# D2R.net
KiCad netlist of a schematic drawn in EAGLE
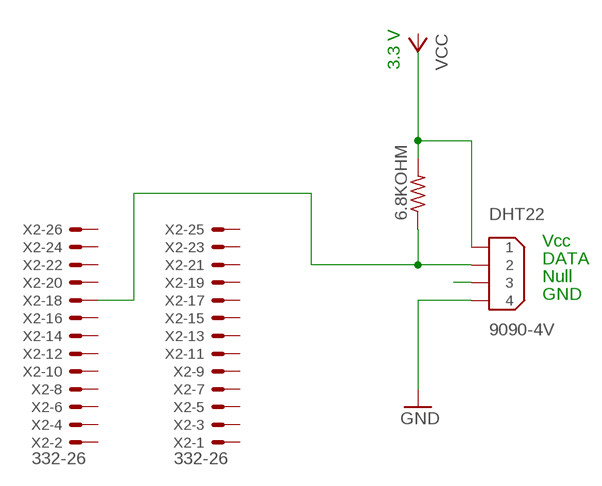
[diagram p0: schematic, sheet 1]

(export (version "E")
  (design (tool "Eeschema 10.0.6"))
  (components
    (comp (ref "6.8KOHM")
      (value "R-US_0207/10")
      (footprint "eagle-import:0207_10")
      (libsource (lib "eagle-import") (part "R-US_0207/10"))
    )
    (comp (ref "DHT22")
      (value "9090-4V")
      (footprint "eagle-import:9090-4V")
      (libsource (lib "eagle-import") (part "9090-4V"))
    )
    (comp (ref "X2")
      (value "332-26")
      (footprint "eagle-import:332-26")
      (libsource (lib "eagle-import") (part "332-26"))
    )
  )
  (nets
    (net (code "1") (name "GND") (class "Default")
      (node (ref "DHT22") (pin "4") (pinfunction "4_4") (pintype "passive"))
    )
    (net (code "2") (name "Net-(6.8KOHM-Pad2)") (class "Default")
      (node (ref "6.8KOHM") (pin "2") (pinfunction "2_2") (pintype "passive"))
      (node (ref "DHT22") (pin "1") (pinfunction "1_1") (pintype "passive"))
    )
    (net (code "3") (name "Net-(X2J-S)") (class "Default")
      (node (ref "6.8KOHM") (pin "1") (pinfunction "1_1") (pintype "passive"))
      (node (ref "DHT22") (pin "2") (pinfunction "2_2") (pintype "passive"))
      (node (ref "X2") (pin "18") (pinfunction "S_18") (pintype "passive"))
    )
    (net (code "5") (name "unconnected-(DHT22-Pad3)") (class "Default")
      (node (ref "DHT22") (pin "3") (pinfunction "3_3") (pintype "passive"))
    )
    (net (code "6") (name "unconnected-(X2A-S-Pad1)") (class "Default")
      (node (ref "X2") (pin "1") (pinfunction "S_1") (pintype "passive"))
    )
    (net (code "7") (name "unconnected-(X2B-S-Pad10)") (class "Default")
      (node (ref "X2") (pin "10") (pinfunction "S_10") (pintype "passive"))
    )
    (net (code "8") (name "unconnected-(X2C-S-Pad11)") (class "Default")
      (node (ref "X2") (pin "11") (pinfunction "S_11") (pintype "passive"))
    )
    (net (code "9") (name "unconnected-(X2D-S-Pad12)") (class "Default")
      (node (ref "X2") (pin "12") (pinfunction "S_12") (pintype "passive"))
    )
    (net (code "10") (name "unconnected-(X2E-S-Pad13)") (class "Default")
      (node (ref "X2") (pin "13") (pinfunction "S_13") (pintype "passive"))
    )
    (net (code "11") (name "unconnected-(X2F-S-Pad14)") (class "Default")
      (node (ref "X2") (pin "14") (pinfunction "S_14") (pintype "passive"))
    )
    (net (code "12") (name "unconnected-(X2G-S-Pad15)") (class "Default")
      (node (ref "X2") (pin "15") (pinfunction "S_15") (pintype "passive"))
    )
    (net (code "13") (name "unconnected-(X2H-S-Pad16)") (class "Default")
      (node (ref "X2") (pin "16") (pinfunction "S_16") (pintype "passive"))
    )
    (net (code "14") (name "unconnected-(X2I-S-Pad17)") (class "Default")
      (node (ref "X2") (pin "17") (pinfunction "S_17") (pintype "passive"))
    )
    (net (code "15") (name "unconnected-(X2K-S-Pad19)") (class "Default")
      (node (ref "X2") (pin "19") (pinfunction "S_19") (pintype "passive"))
    )
    (net (code "16") (name "unconnected-(X2L-S-Pad2)") (class "Default")
      (node (ref "X2") (pin "2") (pinfunction "S_2") (pintype "passive"))
    )
    (net (code "17") (name "unconnected-(X2M-S-Pad20)") (class "Default")
      (node (ref "X2") (pin "20") (pinfunction "S_20") (pintype "passive"))
    )
    (net (code "18") (name "unconnected-(X2N-S-Pad21)") (class "Default")
      (node (ref "X2") (pin "21") (pinfunction "S_21") (pintype "passive"))
    )
    (net (code "19") (name "unconnected-(X2O-S-Pad22)") (class "Default")
      (node (ref "X2") (pin "22") (pinfunction "S_22") (pintype "passive"))
    )
    (net (code "20") (name "unconnected-(X2P-S-Pad23)") (class "Default")
      (node (ref "X2") (pin "23") (pinfunction "S_23") (pintype "passive"))
    )
    (net (code "21") (name "unconnected-(X2Q-S-Pad24)") (class "Default")
      (node (ref "X2") (pin "24") (pinfunction "S_24") (pintype "passive"))
    )
    (net (code "22") (name "unconnected-(X2R-S-Pad25)") (class "Default")
      (node (ref "X2") (pin "25") (pinfunction "S_25") (pintype "passive"))
    )
    (net (code "23") (name "unconnected-(X2S-S-Pad26)") (class "Default")
      (node (ref "X2") (pin "26") (pinfunction "S_26") (pintype "passive"))
    )
    (net (code "24") (name "unconnected-(X2T-S-Pad3)") (class "Default")
      (node (ref "X2") (pin "3") (pinfunction "S_3") (pintype "passive"))
    )
    (net (code "25") (name "unconnected-(X2U-S-Pad4)") (class "Default")
      (node (ref "X2") (pin "4") (pinfunction "S_4") (pintype "passive"))
    )
    (net (code "26") (name "unconnected-(X2V-S-Pad5)") (class "Default")
      (node (ref "X2") (pin "5") (pinfunction "S_5") (pintype "passive"))
    )
    (net (code "27") (name "unconnected-(X2W-S-Pad6)") (class "Default")
      (node (ref "X2") (pin "6") (pinfunction "S_6") (pintype "passive"))
    )
    (net (code "28") (name "unconnected-(X2X-S-Pad7)") (class "Default")
      (node (ref "X2") (pin "7") (pinfunction "S_7") (pintype "passive"))
    )
    (net (code "29") (name "unconnected-(X2Y-S-Pad8)") (class "Default")
      (node (ref "X2") (pin "8") (pinfunction "S_8") (pintype "passive"))
    )
    (net (code "30") (name "unconnected-(X2Z-S-Pad9)") (class "Default")
      (node (ref "X2") (pin "9") (pinfunction "S_9") (pintype "passive"))
    )
  )
)
